# untitled.net
KiCad netlist of a schematic drawn in EAGLE
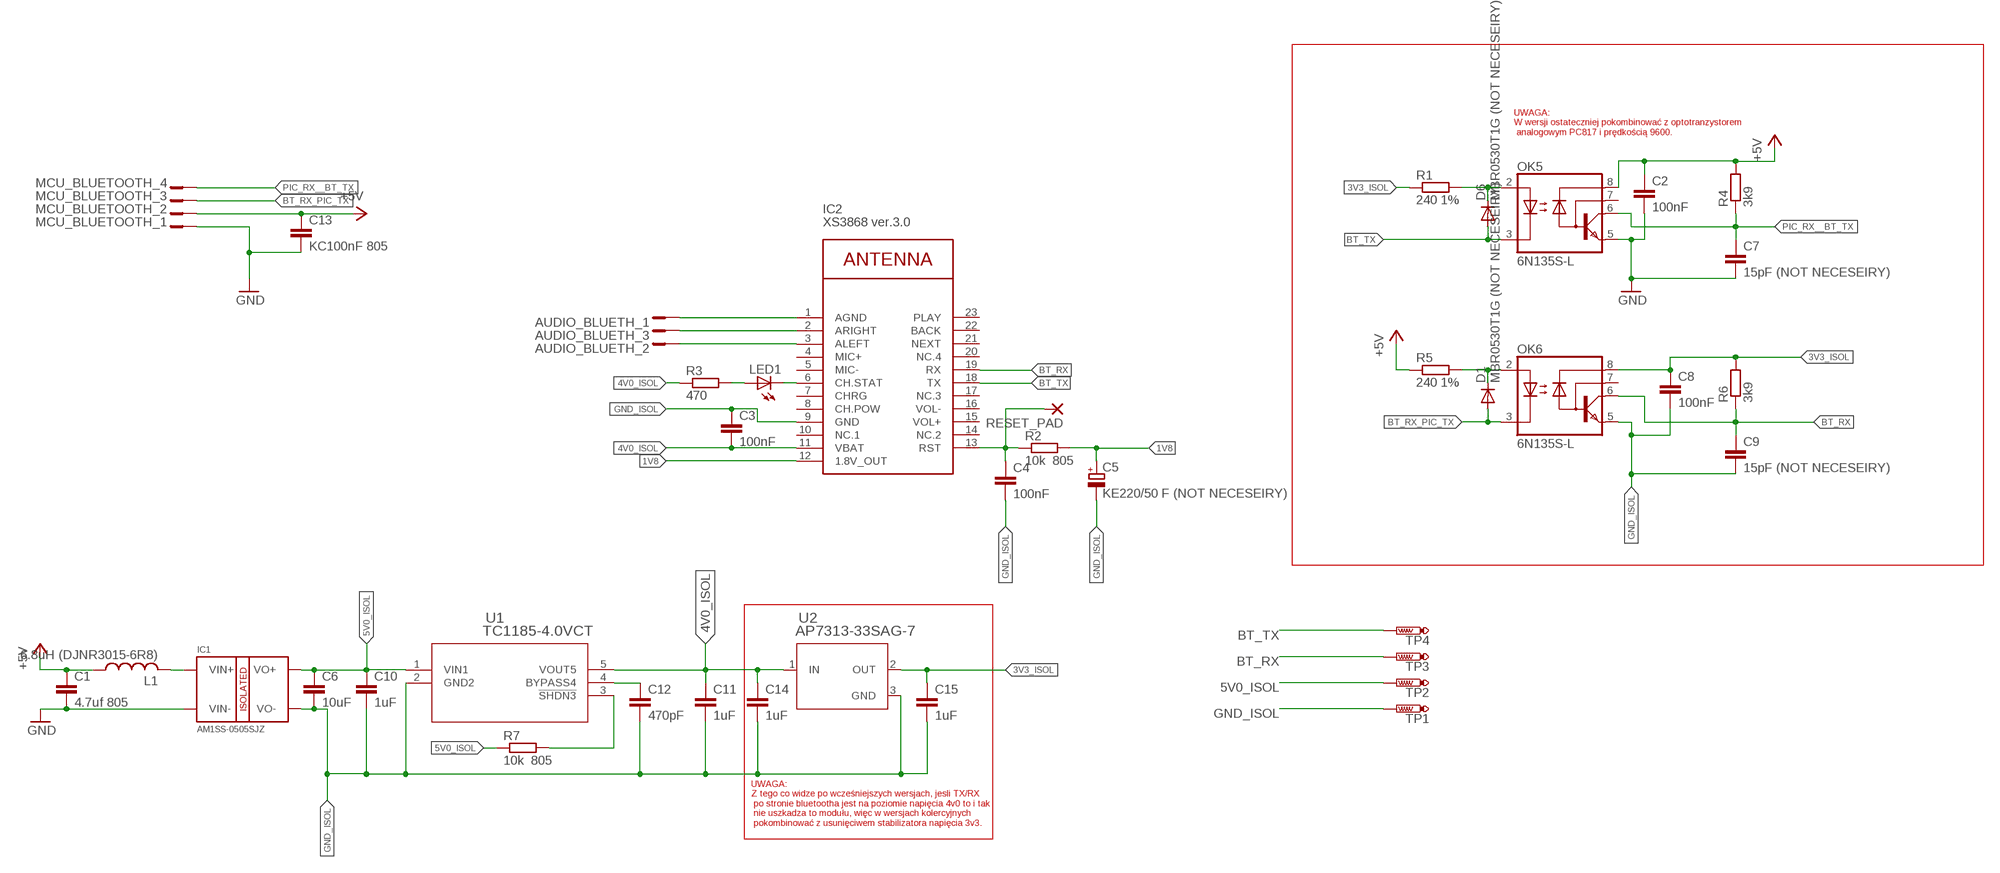
[diagram p0: schematic, sheet 1, part 1 of 2]
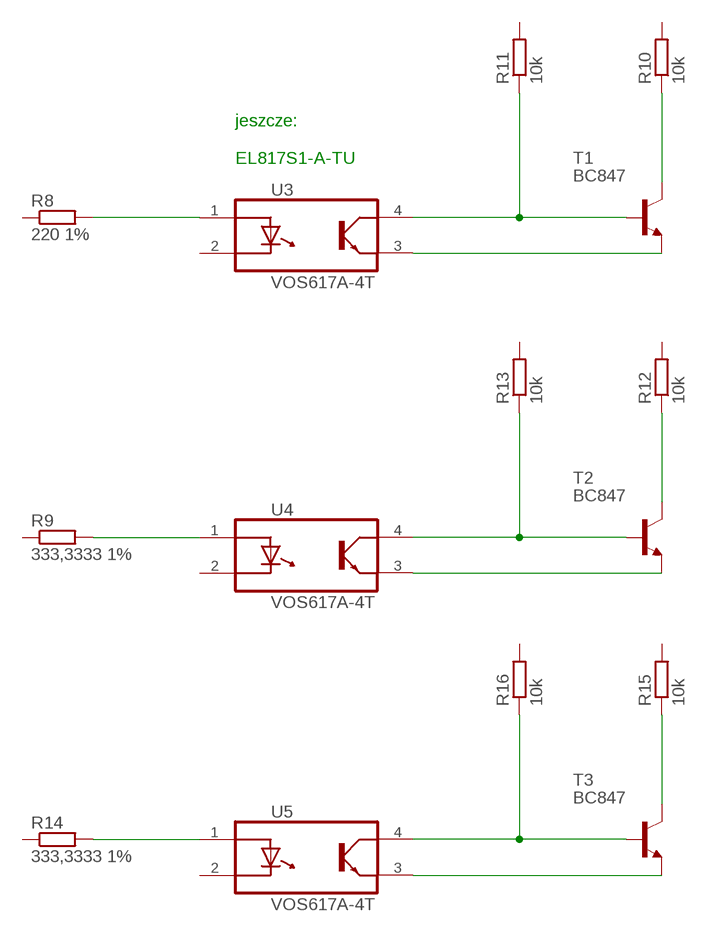
[diagram p1: schematic, sheet 1, part 2 of 2]

(export (version "E")
  (design (tool "Eeschema 10.0.6"))
  (components
    (comp (ref "AUDIO_BLUETH")
      (value "JST_3_PIN_B3B-PH-KS")
      (footprint "eagle-import:B3B-PH-KS")
      (libsource (lib "eagle-import") (part "JST_3_PIN_B3B-PH-KS"))
    )
    (comp (ref "C1")
      (value "4.7uf 805")
      (footprint "eagle-import:C0805")
      (libsource (lib "eagle-import") (part "C-EUC0805"))
    )
    (comp (ref "C2")
      (value "100nF")
      (footprint "eagle-import:C0805")
      (libsource (lib "eagle-import") (part "resistor_C-EUC0805"))
    )
    (comp (ref "C3")
      (value "100nF")
      (footprint "eagle-import:C0805")
      (libsource (lib "eagle-import") (part "resistor_C-EUC0805"))
    )
    (comp (ref "C4")
      (value "100nF")
      (footprint "eagle-import:C0805")
      (libsource (lib "eagle-import") (part "resistor_C-EUC0805"))
    )
    (comp (ref "C5")
      (value "KE220/50 F (NOT NECESEIRY)")
      (footprint "eagle-import:PANASONIC_G")
      (libsource (lib "eagle-import") (part "CPOL-EUG"))
    )
    (comp (ref "C6")
      (value "10uF")
      (footprint "eagle-import:C0805")
      (libsource (lib "eagle-import") (part "resistor_C-EUC0805"))
    )
    (comp (ref "C7")
      (value "15pF (NOT NECESEIRY)")
      (footprint "eagle-import:C0805")
      (libsource (lib "eagle-import") (part "resistor_C-EUC0805"))
    )
    (comp (ref "C8")
      (value "100nF")
      (footprint "eagle-import:C0805")
      (libsource (lib "eagle-import") (part "resistor_C-EUC0805"))
    )
    (comp (ref "C9")
      (value "15pF (NOT NECESEIRY)")
      (footprint "eagle-import:C0805")
      (libsource (lib "eagle-import") (part "resistor_C-EUC0805"))
    )
    (comp (ref "C10")
      (value "1uF")
      (footprint "eagle-import:C0805")
      (libsource (lib "eagle-import") (part "resistor_C-EUC0805"))
    )
    (comp (ref "C11")
      (value "1uF")
      (footprint "eagle-import:C0805")
      (libsource (lib "eagle-import") (part "resistor_C-EUC0805"))
    )
    (comp (ref "C12")
      (value "470pF")
      (footprint "eagle-import:C0805")
      (libsource (lib "eagle-import") (part "resistor_C-EUC0805"))
    )
    (comp (ref "C13")
      (value "KC100nF 805")
      (footprint "eagle-import:C0805")
      (libsource (lib "eagle-import") (part "C-EUC0805"))
    )
    (comp (ref "C14")
      (value "1uF")
      (footprint "eagle-import:C0805")
      (libsource (lib "eagle-import") (part "resistor_C-EUC0805"))
    )
    (comp (ref "C15")
      (value "1uF")
      (footprint "eagle-import:C0805")
      (libsource (lib "eagle-import") (part "resistor_C-EUC0805"))
    )
    (comp (ref "D1")
      (value "MBR0530T1G (NOT NECESEIRY)")
      (footprint "eagle-import:SOD123")
      (libsource (lib "eagle-import") (part "MBR0520LT"))
    )
    (comp (ref "D6")
      (value "MBR0530T1G (NOT NECESEIRY)")
      (footprint "eagle-import:SOD123")
      (libsource (lib "eagle-import") (part "MBR0520LT"))
    )
    (comp (ref "IC1")
      (value "AM1SS-0505SJZ")
      (footprint "eagle-import:SIP4")
      (libsource (lib "eagle-import") (part "AM1SS-0503S-NZ"))
    )
    (comp (ref "IC2")
      (value "XS3868 ver.3.0")
      (footprint "eagle-import:WIRELESS-BLUETOOTH-XS3868")
      (libsource (lib "eagle-import") (part "WIRELESS-BLUETOOTH-XS3868"))
    )
    (comp (ref "L1")
      (value "6.8uH (DJNR3015-6R8)")
      (footprint "eagle-import:L3230M")
      (libsource (lib "eagle-import") (part "L-USL3230M"))
    )
    (comp (ref "LED1")
      (value "LEDSMART-LED")
      (footprint "eagle-import:SMART-LED")
      (libsource (lib "eagle-import") (part "LEDSMART-LED"))
    )
    (comp (ref "MCU_BLUETOOTH")
      (value "JST_4_PIN_B4B-PH-KS")
      (footprint "eagle-import:B4B-PH-KS")
      (libsource (lib "eagle-import") (part "JST_4_PIN_B4B-PH-KS"))
    )
    (comp (ref "OK5")
      (value "6N135S-L")
      (footprint "eagle-import:DIL8-SMD")
      (libsource (lib "eagle-import") (part "6N135DIL8-SMD"))
    )
    (comp (ref "OK6")
      (value "6N135S-L")
      (footprint "eagle-import:DIL8-SMD")
      (libsource (lib "eagle-import") (part "6N135DIL8-SMD"))
    )
    (comp (ref "R1")
      (value "240 1%")
      (footprint "eagle-import:M0805")
      (libsource (lib "eagle-import") (part "R-EU_M0805"))
    )
    (comp (ref "R2")
      (value "10k 805")
      (footprint "eagle-import:M0805")
      (libsource (lib "eagle-import") (part "R-EU_M0805"))
    )
    (comp (ref "R3")
      (value "470")
      (footprint "eagle-import:M0805")
      (libsource (lib "eagle-import") (part "R-EU_M0805"))
    )
    (comp (ref "R4")
      (value "3k9")
      (footprint "eagle-import:M0805")
      (libsource (lib "eagle-import") (part "R-EU_M0805"))
    )
    (comp (ref "R5")
      (value "240 1%")
      (footprint "eagle-import:M0805")
      (libsource (lib "eagle-import") (part "R-EU_M0805"))
    )
    (comp (ref "R6")
      (value "3k9")
      (footprint "eagle-import:M0805")
      (libsource (lib "eagle-import") (part "R-EU_M0805"))
    )
    (comp (ref "R7")
      (value "10k 805")
      (footprint "eagle-import:M0805")
      (libsource (lib "eagle-import") (part "R-EU_M0805"))
    )
    (comp (ref "R8")
      (value "220 1%")
      (footprint "eagle-import:M0805")
      (libsource (lib "eagle-import") (part "R-EU_M0805"))
    )
    (comp (ref "R9")
      (value "333,3333 1%")
      (footprint "eagle-import:M0805")
      (libsource (lib "eagle-import") (part "R-EU_M0805"))
    )
    (comp (ref "R10")
      (value "10k")
      (footprint "eagle-import:M0805")
      (libsource (lib "eagle-import") (part "R-EU_M0805"))
    )
    (comp (ref "R11")
      (value "10k")
      (footprint "eagle-import:M0805")
      (libsource (lib "eagle-import") (part "R-EU_M0805"))
    )
    (comp (ref "R12")
      (value "10k")
      (footprint "eagle-import:M0805")
      (libsource (lib "eagle-import") (part "R-EU_M0805"))
    )
    (comp (ref "R13")
      (value "10k")
      (footprint "eagle-import:M0805")
      (libsource (lib "eagle-import") (part "R-EU_M0805"))
    )
    (comp (ref "R14")
      (value "333,3333 1%")
      (footprint "eagle-import:M0805")
      (libsource (lib "eagle-import") (part "R-EU_M0805"))
    )
    (comp (ref "R15")
      (value "10k")
      (footprint "eagle-import:M0805")
      (libsource (lib "eagle-import") (part "R-EU_M0805"))
    )
    (comp (ref "R16")
      (value "10k")
      (footprint "eagle-import:M0805")
      (libsource (lib "eagle-import") (part "R-EU_M0805"))
    )
    (comp (ref "RESET_PAD")
      (value "SMD2")
      (footprint "eagle-import:SMD1,27-2,54")
      (libsource (lib "eagle-import") (part "SMD2"))
    )
    (comp (ref "T1")
      (value "BC847")
      (footprint "eagle-import:SOT23")
      (libsource (lib "eagle-import") (part "BC847"))
    )
    (comp (ref "T2")
      (value "BC847")
      (footprint "eagle-import:SOT23")
      (libsource (lib "eagle-import") (part "BC847"))
    )
    (comp (ref "T3")
      (value "BC847")
      (footprint "eagle-import:SOT23")
      (libsource (lib "eagle-import") (part "BC847"))
    )
    (comp (ref "TP1")
      (value "PTR1B1,27")
      (footprint "eagle-import:B1,27")
      (libsource (lib "eagle-import") (part "PTR1B1,27"))
    )
    (comp (ref "TP2")
      (value "PTR1B1,27")
      (footprint "eagle-import:B1,27")
      (libsource (lib "eagle-import") (part "PTR1B1,27"))
    )
    (comp (ref "TP3")
      (value "PTR1B1,27")
      (footprint "eagle-import:B1,27")
      (libsource (lib "eagle-import") (part "PTR1B1,27"))
    )
    (comp (ref "TP4")
      (value "PTR1B1,27")
      (footprint "eagle-import:B1,27")
      (libsource (lib "eagle-import") (part "PTR1B1,27"))
    )
    (comp (ref "U1")
      (value "TC1185-4.0VCT")
      (footprint "eagle-import:SOT-23-5_MC-M")
      (fields (field (name "MANUFACTURER_PART_NUMBER") "TC1185X.XXCT713"))
      (libsource (lib "eagle-import") (part "TC1185-X.XXCT713SOT-23-5_MC-M"))
    )
    (comp (ref "U2")
      (value "AP7313-33SAG-7")
      (footprint "eagle-import:SOT-23")
      (fields (field (name "MANUFACTURER_PART_NUMBER") "AP731333SAG7"))
      (libsource (lib "eagle-import") (part "AP7313-33SAG-7"))
    )
    (comp (ref "U3")
      (value "VOS617A-4T")
      (footprint "eagle-import:SOIC127P700X210-4N")
      (fields
        (field (name "DIGI-KEY_PART_NUMBER") "VOS617A-4TCT-ND")
        (field (name "MF") "Vishay Semiconductor")
      )
      (libsource (lib "eagle-import") (part "VOS617A-4T"))
    )
    (comp (ref "U4")
      (value "VOS617A-4T")
      (footprint "eagle-import:SOIC127P700X210-4N")
      (fields
        (field (name "DIGI-KEY_PART_NUMBER") "VOS617A-4TCT-ND")
        (field (name "MF") "Vishay Semiconductor")
      )
      (libsource (lib "eagle-import") (part "VOS617A-4T"))
    )
    (comp (ref "U5")
      (value "VOS617A-4T")
      (footprint "eagle-import:SOIC127P700X210-4N")
      (fields
        (field (name "DIGI-KEY_PART_NUMBER") "VOS617A-4TCT-ND")
        (field (name "MF") "Vishay Semiconductor")
      )
      (libsource (lib "eagle-import") (part "VOS617A-4T"))
    )
  )
  (nets
    (net (code "1") (name "+5V") (class "Default")
      (node (ref "C1") (pin "1") (pinfunction "1_1") (pintype "passive"))
      (node (ref "C13") (pin "1") (pinfunction "1_1") (pintype "passive"))
      (node (ref "C2") (pin "1") (pinfunction "1_1") (pintype "passive"))
      (node (ref "L1") (pin "1") (pinfunction "1_1") (pintype "passive"))
      (node (ref "MCU_BLUETOOTH") (pin "P$2") (pinfunction "P$1_P$2") (pintype "bidirectional"))
      (node (ref "OK5") (pin "8") (pinfunction "VCC_8") (pintype "passive"))
      (node (ref "R4") (pin "2") (pinfunction "2_2") (pintype "passive"))
      (node (ref "R5") (pin "1") (pinfunction "1_1") (pintype "passive"))
    )
    (net (code "2") (name "1V8") (class "Default")
      (node (ref "C5") (pin "+") (pinfunction "+_+") (pintype "passive"))
      (node (ref "IC2") (pin "12") (pinfunction "1.8V_OUT_12") (pintype "power_in"))
      (node (ref "R2") (pin "2") (pinfunction "2_2") (pintype "passive"))
    )
    (net (code "3") (name "3V3_ISOL") (class "Default")
      (node (ref "C15") (pin "1") (pinfunction "1_1") (pintype "passive"))
      (node (ref "C8") (pin "1") (pinfunction "1_1") (pintype "passive"))
      (node (ref "OK6") (pin "8") (pinfunction "VCC_8") (pintype "passive"))
      (node (ref "R1") (pin "1") (pinfunction "1_1") (pintype "passive"))
      (node (ref "R6") (pin "2") (pinfunction "2_2") (pintype "passive"))
      (node (ref "U2") (pin "2") (pinfunction "OUT_2") (pintype "output"))
    )
    (net (code "4") (name "4V0_ISOL") (class "Default")
      (node (ref "C11") (pin "1") (pinfunction "1_1") (pintype "passive"))
      (node (ref "C14") (pin "1") (pinfunction "1_1") (pintype "passive"))
      (node (ref "C3") (pin "2") (pinfunction "2_2") (pintype "passive"))
      (node (ref "IC2") (pin "11") (pinfunction "VBAT_11") (pintype "power_in"))
      (node (ref "R3") (pin "1") (pinfunction "1_1") (pintype "passive"))
      (node (ref "U1") (pin "5") (pinfunction "VOUT5_5") (pintype "passive"))
      (node (ref "U2") (pin "1") (pinfunction "IN_1") (pintype "input"))
    )
    (net (code "5") (name "5V0_ISOL") (class "Default")
      (node (ref "C10") (pin "1") (pinfunction "1_1") (pintype "passive"))
      (node (ref "C6") (pin "1") (pinfunction "1_1") (pintype "passive"))
      (node (ref "IC1") (pin "P$4") (pinfunction "VO+_P$4") (pintype "bidirectional"))
      (node (ref "R7") (pin "1") (pinfunction "1_1") (pintype "passive"))
      (node (ref "TP2") (pin "TP") (pinfunction "TP_TP") (pintype "input"))
      (node (ref "U1") (pin "1") (pinfunction "VIN1_1") (pintype "passive"))
    )
    (net (code "6") (name "BT_RX") (class "Default")
      (node (ref "C9") (pin "1") (pinfunction "1_1") (pintype "passive"))
      (node (ref "IC2") (pin "19") (pinfunction "RX_19") (pintype "bidirectional"))
      (node (ref "OK6") (pin "6") (pinfunction "VO_6") (pintype "passive"))
      (node (ref "R6") (pin "1") (pinfunction "1_1") (pintype "passive"))
      (node (ref "TP3") (pin "TP") (pinfunction "TP_TP") (pintype "input"))
    )
    (net (code "7") (name "BT_RX_PIC_TX") (class "Default")
      (node (ref "D1") (pin "A") (pinfunction "A_A") (pintype "passive"))
      (node (ref "MCU_BLUETOOTH") (pin "P$3") (pinfunction "P$1_P$3") (pintype "bidirectional"))
      (node (ref "OK6") (pin "3") (pinfunction "C_3") (pintype "passive"))
    )
    (net (code "8") (name "BT_TX") (class "Default")
      (node (ref "D6") (pin "A") (pinfunction "A_A") (pintype "passive"))
      (node (ref "IC2") (pin "18") (pinfunction "TX_18") (pintype "bidirectional"))
      (node (ref "OK5") (pin "3") (pinfunction "C_3") (pintype "passive"))
      (node (ref "TP4") (pin "TP") (pinfunction "TP_TP") (pintype "input"))
    )
    (net (code "9") (name "GND") (class "Default")
      (node (ref "C1") (pin "2") (pinfunction "2_2") (pintype "passive"))
      (node (ref "C13") (pin "2") (pinfunction "2_2") (pintype "passive"))
      (node (ref "C2") (pin "2") (pinfunction "2_2") (pintype "passive"))
      (node (ref "C7") (pin "2") (pinfunction "2_2") (pintype "passive"))
      (node (ref "IC1") (pin "P$1") (pinfunction "VIN-_P$1") (pintype "bidirectional"))
      (node (ref "MCU_BLUETOOTH") (pin "P$1") (pinfunction "P$1_P$1") (pintype "bidirectional"))
      (node (ref "OK5") (pin "5") (pinfunction "GND_5") (pintype "passive"))
    )
    (net (code "10") (name "GND_ISOL") (class "Default")
      (node (ref "C10") (pin "2") (pinfunction "2_2") (pintype "passive"))
      (node (ref "C11") (pin "2") (pinfunction "2_2") (pintype "passive"))
      (node (ref "C12") (pin "2") (pinfunction "2_2") (pintype "passive"))
      (node (ref "C14") (pin "2") (pinfunction "2_2") (pintype "passive"))
      (node (ref "C15") (pin "2") (pinfunction "2_2") (pintype "passive"))
      (node (ref "C3") (pin "1") (pinfunction "1_1") (pintype "passive"))
      (node (ref "C4") (pin "2") (pinfunction "2_2") (pintype "passive"))
      (node (ref "C5") (pin "-") (pinfunction "-_-") (pintype "passive"))
      (node (ref "C6") (pin "2") (pinfunction "2_2") (pintype "passive"))
      (node (ref "C8") (pin "2") (pinfunction "2_2") (pintype "passive"))
      (node (ref "C9") (pin "2") (pinfunction "2_2") (pintype "passive"))
      (node (ref "IC1") (pin "P$3") (pinfunction "VO-_P$3") (pintype "bidirectional"))
      (node (ref "IC2") (pin "9") (pinfunction "GND_9") (pintype "power_in"))
      (node (ref "OK6") (pin "5") (pinfunction "GND_5") (pintype "passive"))
      (node (ref "TP1") (pin "TP") (pinfunction "TP_TP") (pintype "input"))
      (node (ref "U1") (pin "2") (pinfunction "GND2_2") (pintype "passive"))
      (node (ref "U2") (pin "3") (pinfunction "GND_3") (pintype "power_in"))
    )
    (net (code "11") (name "Net-(AUDIO_BLUETHB-P$1)") (class "Default")
      (node (ref "AUDIO_BLUETH") (pin "P$2") (pinfunction "P$1_P$2") (pintype "bidirectional"))
      (node (ref "IC2") (pin "3") (pinfunction "ALEFT_3") (pintype "output"))
    )
    (net (code "12") (name "Net-(AUDIO_BLUETHC-P$1)") (class "Default")
      (node (ref "AUDIO_BLUETH") (pin "P$3") (pinfunction "P$1_P$3") (pintype "bidirectional"))
      (node (ref "IC2") (pin "2") (pinfunction "ARIGHT_2") (pintype "output"))
    )
    (net (code "13") (name "Net-(IC1-VIN+)") (class "Default")
      (node (ref "IC1") (pin "P$2") (pinfunction "VIN+_P$2") (pintype "bidirectional"))
      (node (ref "L1") (pin "2") (pinfunction "2_2") (pintype "passive"))
    )
    (net (code "14") (name "Net-(IC2-AGND)") (class "Default")
      (node (ref "AUDIO_BLUETH") (pin "P$1") (pinfunction "P$1_P$1") (pintype "bidirectional"))
      (node (ref "IC2") (pin "1") (pinfunction "AGND_1") (pintype "power_in"))
    )
    (net (code "15") (name "Net-(IC2-CH.STAT)") (class "Default")
      (node (ref "IC2") (pin "6") (pinfunction "CH.STAT_6") (pintype "bidirectional"))
      (node (ref "LED1") (pin "B") (pinfunction "C_B") (pintype "passive"))
    )
    (net (code "16") (name "Net-(IC2-RST)") (class "Default")
      (node (ref "C4") (pin "1") (pinfunction "1_1") (pintype "passive"))
      (node (ref "IC2") (pin "13") (pinfunction "RST_13") (pintype "power_in"))
      (node (ref "R2") (pin "1") (pinfunction "1_1") (pintype "passive"))
      (node (ref "RESET_PAD") (pin "1") (pinfunction "P_1") (pintype "passive"))
    )
    (net (code "17") (name "Net-(LED1-PadA)") (class "Default")
      (node (ref "LED1") (pin "A") (pinfunction "A_A") (pintype "passive"))
      (node (ref "R3") (pin "2") (pinfunction "2_2") (pintype "passive"))
    )
    (net (code "18") (name "Net-(OK5-A)") (class "Default")
      (node (ref "D6") (pin "C") (pinfunction "C_C") (pintype "passive"))
      (node (ref "OK5") (pin "2") (pinfunction "A_2") (pintype "passive"))
      (node (ref "R1") (pin "2") (pinfunction "2_2") (pintype "passive"))
    )
    (net (code "19") (name "Net-(OK6-A)") (class "Default")
      (node (ref "D1") (pin "C") (pinfunction "C_C") (pintype "passive"))
      (node (ref "OK6") (pin "2") (pinfunction "A_2") (pintype "passive"))
      (node (ref "R5") (pin "2") (pinfunction "2_2") (pintype "passive"))
    )
    (net (code "20") (name "Net-(T1-B)") (class "Default")
      (node (ref "R11") (pin "1") (pinfunction "1_1") (pintype "passive"))
      (node (ref "T1") (pin "1") (pinfunction "B_1") (pintype "passive"))
      (node (ref "U3") (pin "4") (pinfunction "CO_4") (pintype "passive"))
    )
    (net (code "21") (name "Net-(T1-C)") (class "Default")
      (node (ref "R10") (pin "1") (pinfunction "1_1") (pintype "passive"))
      (node (ref "T1") (pin "3") (pinfunction "C_3") (pintype "passive"))
    )
    (net (code "22") (name "Net-(T1-E)") (class "Default")
      (node (ref "T1") (pin "2") (pinfunction "E_2") (pintype "passive"))
      (node (ref "U3") (pin "3") (pinfunction "E_3") (pintype "passive"))
    )
    (net (code "23") (name "Net-(T2-B)") (class "Default")
      (node (ref "R13") (pin "1") (pinfunction "1_1") (pintype "passive"))
      (node (ref "T2") (pin "1") (pinfunction "B_1") (pintype "passive"))
      (node (ref "U4") (pin "4") (pinfunction "CO_4") (pintype "passive"))
    )
    (net (code "24") (name "Net-(T2-C)") (class "Default")
      (node (ref "R12") (pin "1") (pinfunction "1_1") (pintype "passive"))
      (node (ref "T2") (pin "3") (pinfunction "C_3") (pintype "passive"))
    )
    (net (code "25") (name "Net-(T2-E)") (class "Default")
      (node (ref "T2") (pin "2") (pinfunction "E_2") (pintype "passive"))
      (node (ref "U4") (pin "3") (pinfunction "E_3") (pintype "passive"))
    )
    (net (code "26") (name "Net-(T3-B)") (class "Default")
      (node (ref "R16") (pin "1") (pinfunction "1_1") (pintype "passive"))
      (node (ref "T3") (pin "1") (pinfunction "B_1") (pintype "passive"))
      (node (ref "U5") (pin "4") (pinfunction "CO_4") (pintype "passive"))
    )
    (net (code "27") (name "Net-(T3-C)") (class "Default")
      (node (ref "R15") (pin "1") (pinfunction "1_1") (pintype "passive"))
      (node (ref "T3") (pin "3") (pinfunction "C_3") (pintype "passive"))
    )
    (net (code "28") (name "Net-(T3-E)") (class "Default")
      (node (ref "T3") (pin "2") (pinfunction "E_2") (pintype "passive"))
      (node (ref "U5") (pin "3") (pinfunction "E_3") (pintype "passive"))
    )
    (net (code "29") (name "Net-(U1-BYPASS4)") (class "Default")
      (node (ref "C12") (pin "1") (pinfunction "1_1") (pintype "passive"))
      (node (ref "U1") (pin "4") (pinfunction "BYPASS4_4") (pintype "passive"))
    )
    (net (code "30") (name "Net-(U1-~{SHDN3})") (class "Default")
      (node (ref "R7") (pin "2") (pinfunction "2_2") (pintype "passive"))
      (node (ref "U1") (pin "3") (pinfunction "~{SHDN3}_3") (pintype "passive"))
    )
    (net (code "31") (name "Net-(U3-A)") (class "Default")
      (node (ref "R8") (pin "2") (pinfunction "2_2") (pintype "passive"))
      (node (ref "U3") (pin "1") (pinfunction "A_1") (pintype "passive"))
    )
    (net (code "32") (name "Net-(U4-A)") (class "Default")
      (node (ref "R9") (pin "2") (pinfunction "2_2") (pintype "passive"))
      (node (ref "U4") (pin "1") (pinfunction "A_1") (pintype "passive"))
    )
    (net (code "33") (name "Net-(U5-A)") (class "Default")
      (node (ref "R14") (pin "2") (pinfunction "2_2") (pintype "passive"))
      (node (ref "U5") (pin "1") (pinfunction "A_1") (pintype "passive"))
    )
    (net (code "34") (name "PIC_RX__BT_TX") (class "Default")
      (node (ref "C7") (pin "1") (pinfunction "1_1") (pintype "passive"))
      (node (ref "MCU_BLUETOOTH") (pin "P$4") (pinfunction "P$1_P$4") (pintype "bidirectional"))
      (node (ref "OK5") (pin "6") (pinfunction "VO_6") (pintype "passive"))
      (node (ref "R4") (pin "1") (pinfunction "1_1") (pintype "passive"))
    )
    (net (code "35") (name "unconnected-(IC2-BACK-Pad22)") (class "Default")
      (node (ref "IC2") (pin "22") (pinfunction "BACK_22") (pintype "bidirectional"))
    )
    (net (code "36") (name "unconnected-(IC2-CH.POW-Pad8)") (class "Default")
      (node (ref "IC2") (pin "8") (pinfunction "CH.POW_8") (pintype "bidirectional"))
    )
    (net (code "37") (name "unconnected-(IC2-CHRG-Pad7)") (class "Default")
      (node (ref "IC2") (pin "7") (pinfunction "CHRG_7") (pintype "bidirectional"))
    )
    (net (code "38") (name "unconnected-(IC2-MIC+-Pad4)") (class "Default")
      (node (ref "IC2") (pin "4") (pinfunction "MIC+_4") (pintype "bidirectional"))
    )
    (net (code "39") (name "unconnected-(IC2-MIC--Pad5)") (class "Default")
      (node (ref "IC2") (pin "5") (pinfunction "MIC-_5") (pintype "bidirectional"))
    )
    (net (code "40") (name "unconnected-(IC2-NC.1-Pad10)") (class "Default")
      (node (ref "IC2") (pin "10") (pinfunction "NC.1_10") (pintype "passive"))
    )
    (net (code "41") (name "unconnected-(IC2-NC.2-Pad14)") (class "Default")
      (node (ref "IC2") (pin "14") (pinfunction "NC.2_14") (pintype "passive"))
    )
    (net (code "42") (name "unconnected-(IC2-NC.3-Pad17)") (class "Default")
      (node (ref "IC2") (pin "17") (pinfunction "NC.3_17") (pintype "passive"))
    )
    (net (code "43") (name "unconnected-(IC2-NC.4-Pad20)") (class "Default")
      (node (ref "IC2") (pin "20") (pinfunction "NC.4_20") (pintype "passive"))
    )
    (net (code "44") (name "unconnected-(IC2-NEXT-Pad21)") (class "Default")
      (node (ref "IC2") (pin "21") (pinfunction "NEXT_21") (pintype "bidirectional"))
    )
    (net (code "45") (name "unconnected-(IC2-PLAY-Pad23)") (class "Default")
      (node (ref "IC2") (pin "23") (pinfunction "PLAY_23") (pintype "bidirectional"))
    )
    (net (code "46") (name "unconnected-(IC2-VOL+-Pad15)") (class "Default")
      (node (ref "IC2") (pin "15") (pinfunction "VOL+_15") (pintype "bidirectional"))
    )
    (net (code "47") (name "unconnected-(IC2-VOL--Pad16)") (class "Default")
      (node (ref "IC2") (pin "16") (pinfunction "VOL-_16") (pintype "bidirectional"))
    )
    (net (code "48") (name "unconnected-(OK5-VB-Pad7)") (class "Default")
      (node (ref "OK5") (pin "7") (pinfunction "VB_7") (pintype "passive"))
    )
    (net (code "49") (name "unconnected-(OK6-VB-Pad7)") (class "Default")
      (node (ref "OK6") (pin "7") (pinfunction "VB_7") (pintype "passive"))
    )
    (net (code "50") (name "unconnected-(R8-Pad1)") (class "Default")
      (node (ref "R8") (pin "1") (pinfunction "1_1") (pintype "passive"))
    )
    (net (code "51") (name "unconnected-(R9-Pad1)") (class "Default")
      (node (ref "R9") (pin "1") (pinfunction "1_1") (pintype "passive"))
    )
    (net (code "52") (name "unconnected-(R10-Pad2)") (class "Default")
      (node (ref "R10") (pin "2") (pinfunction "2_2") (pintype "passive"))
    )
    (net (code "53") (name "unconnected-(R11-Pad2)") (class "Default")
      (node (ref "R11") (pin "2") (pinfunction "2_2") (pintype "passive"))
    )
    (net (code "54") (name "unconnected-(R12-Pad2)") (class "Default")
      (node (ref "R12") (pin "2") (pinfunction "2_2") (pintype "passive"))
    )
    (net (code "55") (name "unconnected-(R13-Pad2)") (class "Default")
      (node (ref "R13") (pin "2") (pinfunction "2_2") (pintype "passive"))
    )
    (net (code "56") (name "unconnected-(R14-Pad1)") (class "Default")
      (node (ref "R14") (pin "1") (pinfunction "1_1") (pintype "passive"))
    )
    (net (code "57") (name "unconnected-(R15-Pad2)") (class "Default")
      (node (ref "R15") (pin "2") (pinfunction "2_2") (pintype "passive"))
    )
    (net (code "58") (name "unconnected-(R16-Pad2)") (class "Default")
      (node (ref "R16") (pin "2") (pinfunction "2_2") (pintype "passive"))
    )
    (net (code "59") (name "unconnected-(U3-C-Pad2)") (class "Default")
      (node (ref "U3") (pin "2") (pinfunction "C_2") (pintype "passive"))
    )
    (net (code "60") (name "unconnected-(U4-C-Pad2)") (class "Default")
      (node (ref "U4") (pin "2") (pinfunction "C_2") (pintype "passive"))
    )
    (net (code "61") (name "unconnected-(U5-C-Pad2)") (class "Default")
      (node (ref "U5") (pin "2") (pinfunction "C_2") (pintype "passive"))
    )
  )
)
